# ProDoc_esp32_DWM1000_2025-11-09.net
KiCad netlist of a schematic drawn in EasyEDA Pro
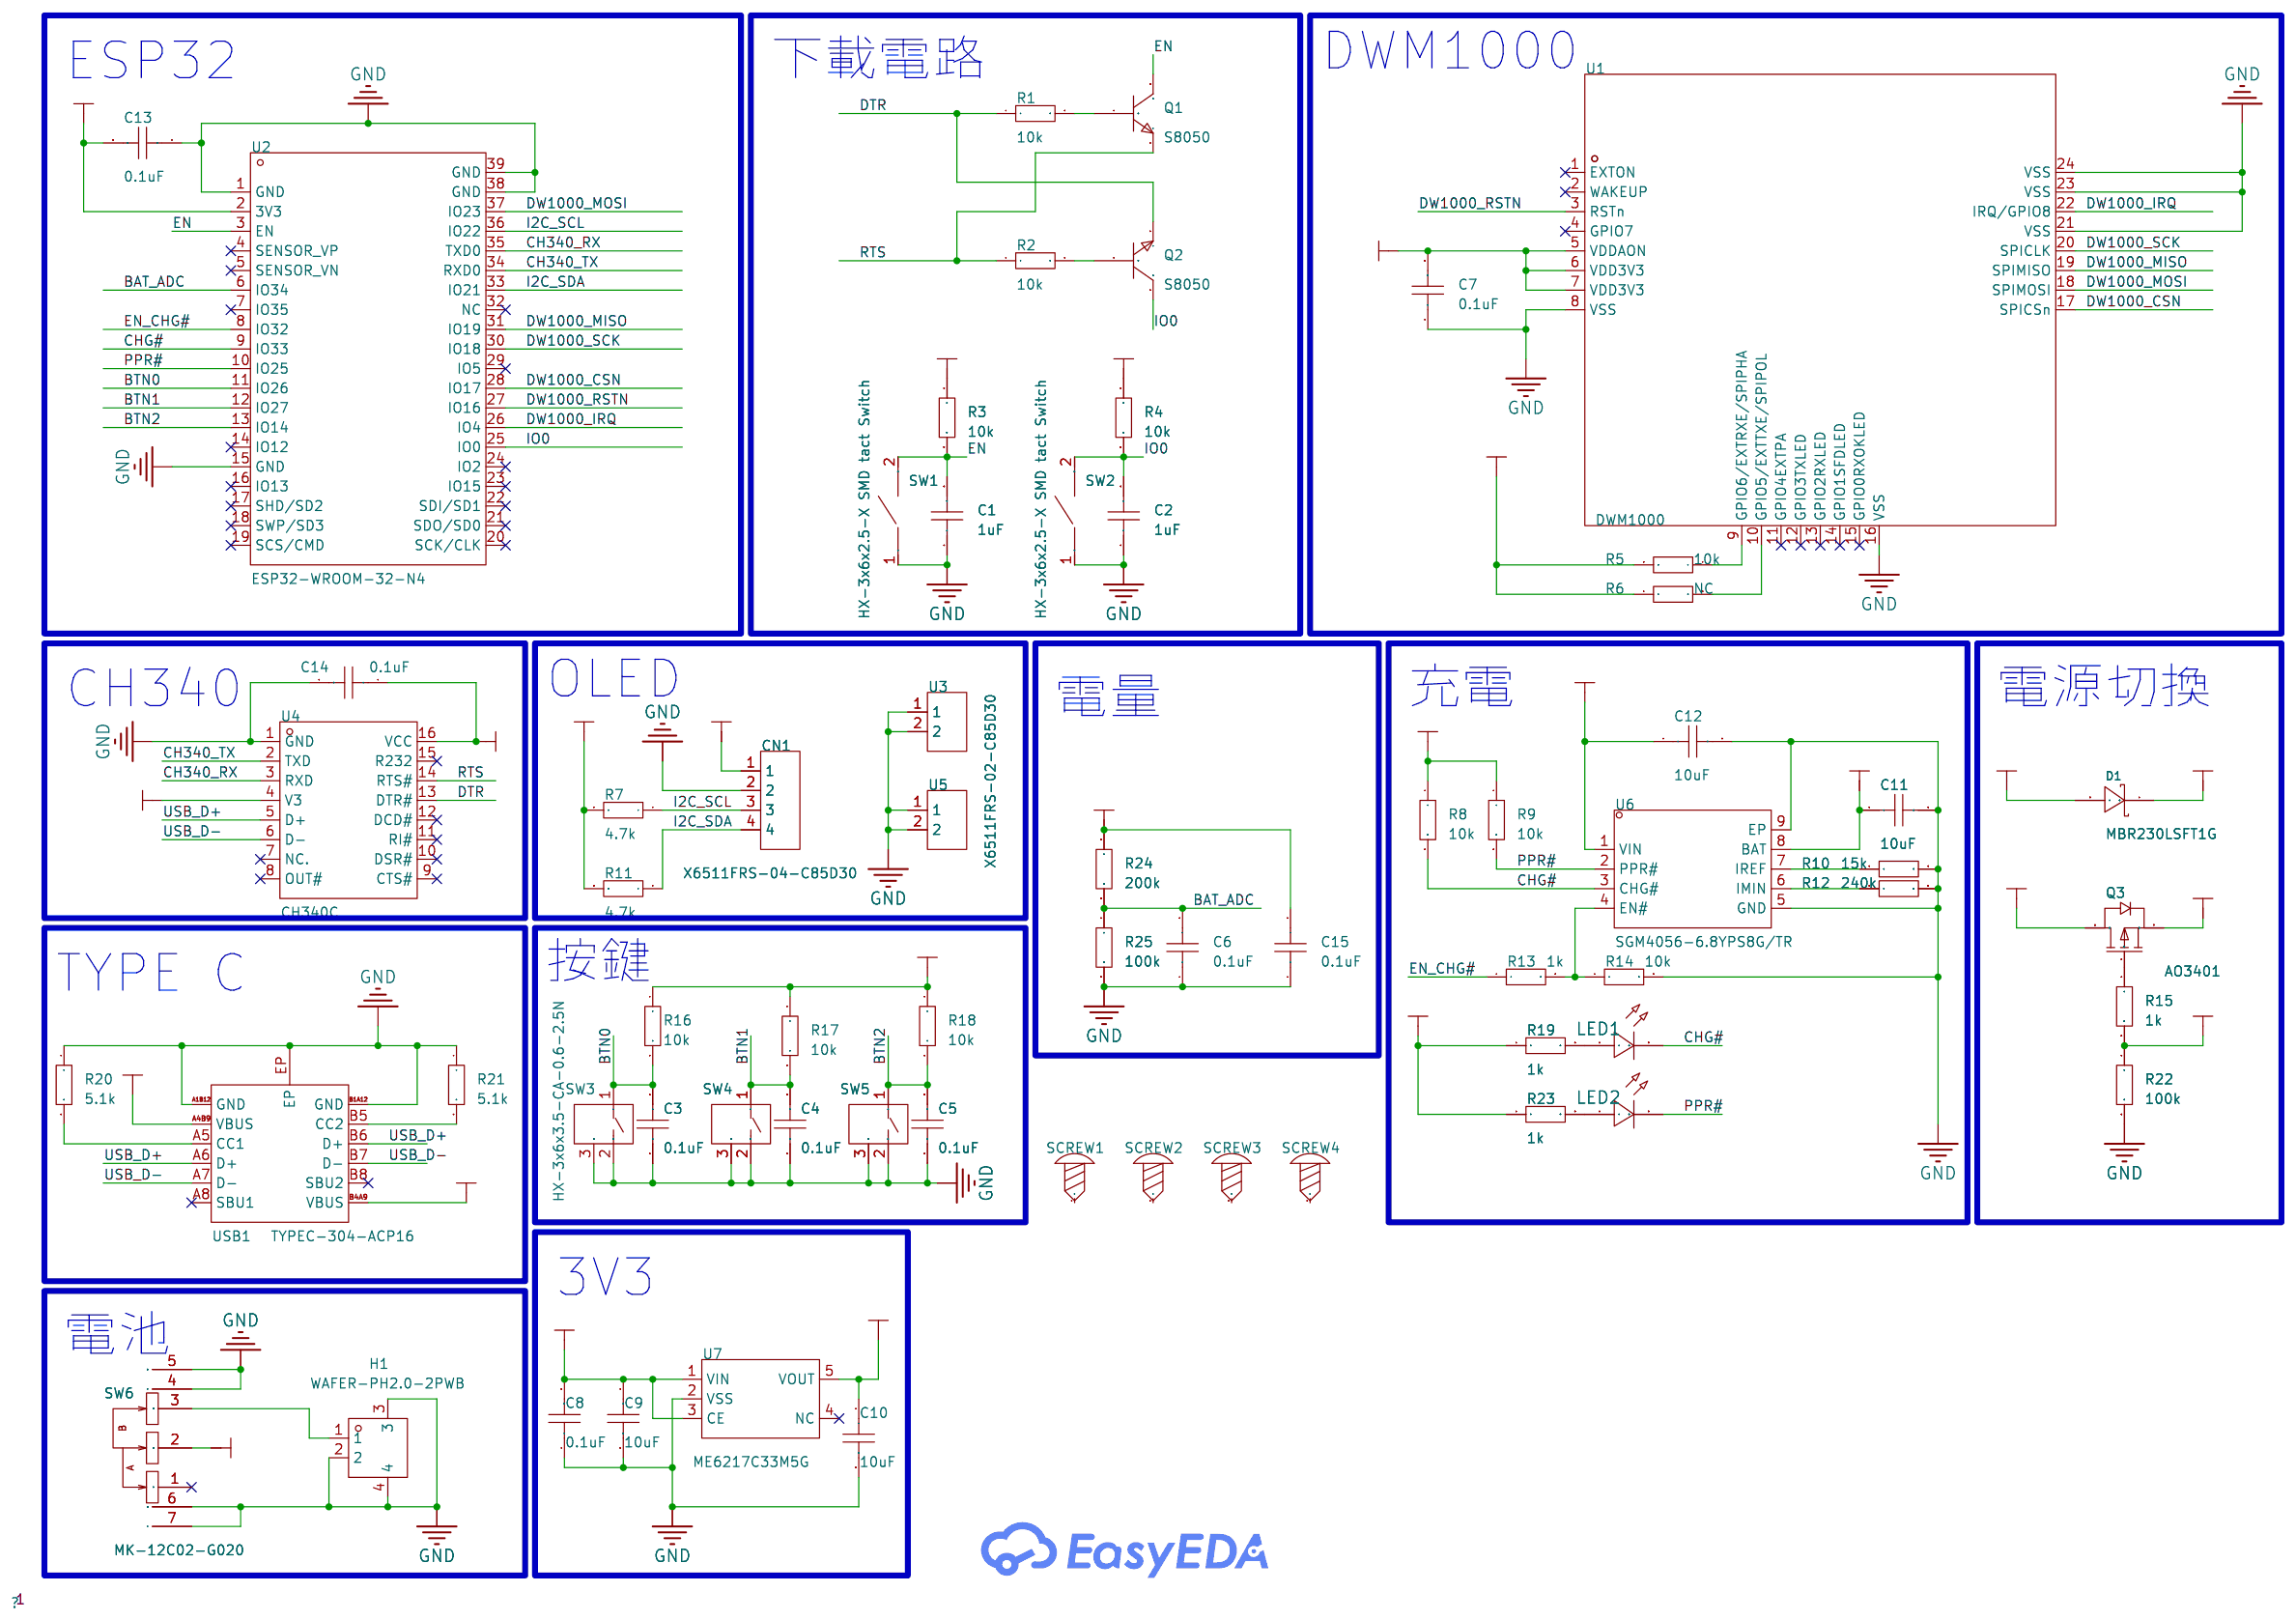
[diagram p0: schematic sheet]

(export (version "E")
  (design (tool "Eeschema 10.0.6"))
  (components
    (comp (ref "C1") (value "1uF") (footprint "easyedapro:C0805") (libsource (lib "easyedapro") (part "CAP")))
    (comp (ref "C2") (value "1uF") (footprint "easyedapro:C0805") (libsource (lib "easyedapro") (part "CAP")))
    (comp (ref "C3")
      (value "0.1uF")
      (footprint "easyedapro:C0805")
      (libsource (lib "easyedapro") (part "CAP"))
    )
    (comp (ref "C4")
      (value "0.1uF")
      (footprint "easyedapro:C0805")
      (libsource (lib "easyedapro") (part "CAP"))
    )
    (comp (ref "C5")
      (value "0.1uF")
      (footprint "easyedapro:C0805")
      (libsource (lib "easyedapro") (part "CAP"))
    )
    (comp (ref "C6")
      (value "0.1uF")
      (footprint "easyedapro:C0805")
      (libsource (lib "easyedapro") (part "CAP"))
    )
    (comp (ref "C7")
      (value "0.1uF")
      (footprint "easyedapro:C0805")
      (libsource (lib "easyedapro") (part "CAP"))
    )
    (comp (ref "C8")
      (value "0.1uF")
      (footprint "easyedapro:C0805")
      (libsource (lib "easyedapro") (part "CAP"))
    )
    (comp (ref "C9")
      (value "10uF")
      (footprint "easyedapro:C0805")
      (libsource (lib "easyedapro") (part "CAP"))
    )
    (comp (ref "C10")
      (value "10uF")
      (footprint "easyedapro:C0805")
      (libsource (lib "easyedapro") (part "CAP"))
    )
    (comp (ref "C11")
      (value "10uF")
      (footprint "easyedapro:C0805")
      (libsource (lib "easyedapro") (part "CAP"))
    )
    (comp (ref "C12")
      (value "10uF")
      (footprint "easyedapro:C0805")
      (libsource (lib "easyedapro") (part "CAP"))
    )
    (comp (ref "C13")
      (value "0.1uF")
      (footprint "easyedapro:C0805")
      (libsource (lib "easyedapro") (part "CAP"))
    )
    (comp (ref "C14")
      (value "0.1uF")
      (footprint "easyedapro:C0805")
      (libsource (lib "easyedapro") (part "CAP"))
    )
    (comp (ref "C15")
      (value "0.1uF")
      (footprint "easyedapro:C0805")
      (libsource (lib "easyedapro") (part "CAP"))
    )
    (comp (ref "CN1")
      (value "X6511FRS-04-C85D30")
      (footprint "easyedapro:HDR-SMD_4P-P2.54-H-F")
      (fields (field (name "Manufacturer") "XKB Connection(中国星坤)"))
      (libsource (lib "easyedapro") (part "X6511FRS-04-C85D30"))
    )
    (comp (ref "D1")
      (value "MBR230LSFT1G")
      (footprint "easyedapro:SOD-123FL_L2.7-W1.8-LS3.8-RD")
      (fields (field (name "Manufacturer") "onsemi(安森美)"))
      (libsource (lib "easyedapro") (part "MBR230LSFT1G"))
    )
    (comp (ref "H1")
      (value "WAFER-PH2.0-2PWB")
      (footprint "easyedapro:CONN-SMD_2P-P2.00_XUNPU_WAFER-PH2.0-2PWB")
      (fields (field (name "Manufacturer") "XUNPU(讯普)"))
      (libsource (lib "easyedapro") (part "WAFER-PH2.0-2PWB"))
    )
    (comp (ref "LED1")
      (value "~")
      (footprint "easyedapro:LED0805-RD_GREEN")
      (libsource (lib "easyedapro") (part "LED_R"))
    )
    (comp (ref "LED2")
      (value "~")
      (footprint "easyedapro:LED0805-RD_GREEN")
      (libsource (lib "easyedapro") (part "LED_R"))
    )
    (comp (ref "Q1")
      (value "S8050")
      (footprint "easyedapro:SOT-23-3_L2.9-W1.3-P1.90-LS2.4-BR")
      (libsource (lib "easyedapro") (part "S8050_C139514"))
    )
    (comp (ref "Q2")
      (value "S8050")
      (footprint "easyedapro:SOT-23-3_L2.9-W1.3-P1.90-LS2.4-BR")
      (libsource (lib "easyedapro") (part "S8050_C139514"))
    )
    (comp (ref "Q3")
      (value "AO3401")
      (footprint "easyedapro:SOT-23-3_L2.9-W1.6-P1.90-LS2.8-BR")
      (fields (field (name "Manufacturer") "BLUE ROCKET(蓝箭)"))
      (libsource (lib "easyedapro") (part "AO3401_C305433"))
    )
    (comp (ref "R1")
      (value "10k")
      (footprint "easyedapro:R0603")
      (fields (field (name "Manufacturer Part") "SCR0805F10K") (field (name "Manufacturer") "VO(翔胜)"))
      (libsource (lib "easyedapro") (part "Res"))
    )
    (comp (ref "R2")
      (value "10k")
      (footprint "easyedapro:R0603")
      (fields (field (name "Manufacturer Part") "SCR0805F10K") (field (name "Manufacturer") "VO(翔胜)"))
      (libsource (lib "easyedapro") (part "Res"))
    )
    (comp (ref "R3") (value "10k") (footprint "easyedapro:R0603") (libsource (lib "easyedapro") (part "Res")))
    (comp (ref "R4") (value "10k") (footprint "easyedapro:R0603") (libsource (lib "easyedapro") (part "Res")))
    (comp (ref "R5")
      (value "10k")
      (footprint "easyedapro:R0603")
      (fields (field (name "Manufacturer Part") "SCR0805F10K") (field (name "Manufacturer") "VO(翔胜)"))
      (libsource (lib "easyedapro") (part "Res"))
    )
    (comp (ref "R6")
      (value "NC")
      (footprint "easyedapro:R0603")
      (fields (field (name "Manufacturer Part") "SCR0805F10K") (field (name "Manufacturer") "VO(翔胜)"))
      (libsource (lib "easyedapro") (part "Res"))
    )
    (comp (ref "R7")
      (value "4.7k")
      (footprint "easyedapro:R0603")
      (fields (field (name "Manufacturer Part") "SCR0805F10K") (field (name "Manufacturer") "VO(翔胜)"))
      (libsource (lib "easyedapro") (part "Res"))
    )
    (comp (ref "R8")
      (value "10k")
      (footprint "easyedapro:R0603")
      (fields (field (name "Manufacturer Part") "SCR0805F10K") (field (name "Manufacturer") "VO(翔胜)"))
      (libsource (lib "easyedapro") (part "Res"))
    )
    (comp (ref "R9")
      (value "10k")
      (footprint "easyedapro:R0603")
      (fields (field (name "Manufacturer Part") "SCR0805F10K") (field (name "Manufacturer") "VO(翔胜)"))
      (libsource (lib "easyedapro") (part "Res"))
    )
    (comp (ref "R10")
      (value "15k")
      (footprint "easyedapro:R0603")
      (fields (field (name "Manufacturer Part") "SCR0805F10K") (field (name "Manufacturer") "VO(翔胜)"))
      (libsource (lib "easyedapro") (part "Res"))
    )
    (comp (ref "R11")
      (value "4.7k")
      (footprint "easyedapro:R0603")
      (fields (field (name "Manufacturer Part") "SCR0805F10K") (field (name "Manufacturer") "VO(翔胜)"))
      (libsource (lib "easyedapro") (part "Res"))
    )
    (comp (ref "R12")
      (value "240k")
      (footprint "easyedapro:R0603")
      (fields (field (name "Manufacturer Part") "SCR0805F10K") (field (name "Manufacturer") "VO(翔胜)"))
      (libsource (lib "easyedapro") (part "Res"))
    )
    (comp (ref "R13")
      (value "1k")
      (footprint "easyedapro:R0603")
      (fields (field (name "Manufacturer Part") "SCR0805F10K") (field (name "Manufacturer") "VO(翔胜)"))
      (libsource (lib "easyedapro") (part "Res"))
    )
    (comp (ref "R14")
      (value "10k")
      (footprint "easyedapro:R0603")
      (libsource (lib "easyedapro") (part "Res"))
    )
    (comp (ref "R15")
      (value "1k")
      (footprint "easyedapro:R0603")
      (fields (field (name "Manufacturer Part") "SCR0805F10K") (field (name "Manufacturer") "VO(翔胜)"))
      (libsource (lib "easyedapro") (part "Res"))
    )
    (comp (ref "R16")
      (value "10k")
      (footprint "easyedapro:R0603")
      (libsource (lib "easyedapro") (part "Res"))
    )
    (comp (ref "R17")
      (value "10k")
      (footprint "easyedapro:R0603")
      (libsource (lib "easyedapro") (part "Res"))
    )
    (comp (ref "R18")
      (value "10k")
      (footprint "easyedapro:R0603")
      (libsource (lib "easyedapro") (part "Res"))
    )
    (comp (ref "R19")
      (value "1k")
      (footprint "easyedapro:R0603")
      (fields (field (name "Manufacturer Part") "SCR0805F10K") (field (name "Manufacturer") "VO(翔胜)"))
      (libsource (lib "easyedapro") (part "Res"))
    )
    (comp (ref "R20")
      (value "5.1k")
      (footprint "easyedapro:R0603")
      (fields (field (name "Manufacturer Part") "SCR0805F10K") (field (name "Manufacturer") "VO(翔胜)"))
      (libsource (lib "easyedapro") (part "Res"))
    )
    (comp (ref "R21")
      (value "5.1k")
      (footprint "easyedapro:R0603")
      (fields (field (name "Manufacturer Part") "SCR0805F10K") (field (name "Manufacturer") "VO(翔胜)"))
      (libsource (lib "easyedapro") (part "Res"))
    )
    (comp (ref "R22")
      (value "100k")
      (footprint "easyedapro:R0603")
      (fields (field (name "Manufacturer Part") "SCR0805F10K") (field (name "Manufacturer") "VO(翔胜)"))
      (libsource (lib "easyedapro") (part "Res"))
    )
    (comp (ref "R23")
      (value "1k")
      (footprint "easyedapro:R0603")
      (fields (field (name "Manufacturer Part") "SCR0805F10K") (field (name "Manufacturer") "VO(翔胜)"))
      (libsource (lib "easyedapro") (part "Res"))
    )
    (comp (ref "R24")
      (value "200k")
      (footprint "easyedapro:R0603")
      (fields (field (name "Manufacturer Part") "SCR0805F10K") (field (name "Manufacturer") "VO(翔胜)"))
      (libsource (lib "easyedapro") (part "Res"))
    )
    (comp (ref "R25")
      (value "100k")
      (footprint "easyedapro:R0603")
      (fields (field (name "Manufacturer Part") "SCR0805F10K") (field (name "Manufacturer") "VO(翔胜)"))
      (libsource (lib "easyedapro") (part "Res"))
    )
    (comp (ref "SCREW1")
      (value "~")
      (footprint "easyedapro:Screw-Hole-M3")
      (libsource (lib "easyedapro") (part "Screw-Hole"))
    )
    (comp (ref "SCREW2")
      (value "~")
      (footprint "easyedapro:Screw-Hole-M3")
      (libsource (lib "easyedapro") (part "Screw-Hole"))
    )
    (comp (ref "SCREW3")
      (value "~")
      (footprint "easyedapro:Screw-Hole-M3")
      (libsource (lib "easyedapro") (part "Screw-Hole"))
    )
    (comp (ref "SCREW4")
      (value "~")
      (footprint "easyedapro:Screw-Hole-M3")
      (libsource (lib "easyedapro") (part "Screw-Hole"))
    )
    (comp (ref "SW1")
      (value "HX-3x6x2.5-X SMD tact Switch")
      (footprint "easyedapro:SW-SMD_HX-3X6X2.5-X")
      (fields (field (name "Manufacturer") "hanxia(韩下)"))
      (libsource (lib "easyedapro") (part "HX-3X6X2.5-X SMD TACT SWITCH"))
    )
    (comp (ref "SW2")
      (value "HX-3x6x2.5-X SMD tact Switch")
      (footprint "easyedapro:SW-SMD_HX-3X6X2.5-X")
      (fields (field (name "Manufacturer") "hanxia(韩下)"))
      (libsource (lib "easyedapro") (part "HX-3X6X2.5-X SMD TACT SWITCH"))
    )
    (comp (ref "SW3")
      (value "HX-3x6x3.5-CA-0.6-2.5N")
      (footprint "easyedapro:SW-SMD_HX-3X6X3.5-CA-0.6-2.5N")
      (fields (field (name "Manufacturer") "hanxia(韩下)"))
      (libsource (lib "easyedapro") (part "HX-3X6X3.5-CA-0.6-2.5N"))
    )
    (comp (ref "SW4")
      (value "HX-3x6x3.5-CA-0.6-2.5N")
      (footprint "easyedapro:SW-SMD_HX-3X6X3.5-CA-0.6-2.5N")
      (fields (field (name "Manufacturer") "hanxia(韩下)"))
      (libsource (lib "easyedapro") (part "HX-3X6X3.5-CA-0.6-2.5N"))
    )
    (comp (ref "SW5")
      (value "HX-3x6x3.5-CA-0.6-2.5N")
      (footprint "easyedapro:SW-SMD_HX-3X6X3.5-CA-0.6-2.5N")
      (fields (field (name "Manufacturer") "hanxia(韩下)"))
      (libsource (lib "easyedapro") (part "HX-3X6X3.5-CA-0.6-2.5N"))
    )
    (comp (ref "SW6")
      (value "MK-12C02-G020")
      (footprint "easyedapro:SW-SMD_MK-12C02-G020")
      (fields (field (name "Manufacturer") "G-Switch(品赞)"))
      (libsource (lib "easyedapro") (part "MK-12C02-G020"))
    )
    (comp (ref "U1")
      (value "DWM1000")
      (footprint "easyedapro:WIRELM-TH_DWM1000")
      (fields (field (name "Manufacturer") "decaWave"))
      (libsource (lib "easyedapro") (part "DWM1000"))
    )
    (comp (ref "U2")
      (value "ESP32-WROOM-32-N4")
      (footprint "easyedapro:WIFIM-SMD_ESP32-WROOM-32-N4")
      (fields (field (name "Manufacturer") "ESPRESSIF(乐鑫)"))
      (libsource (lib "easyedapro") (part "ESP32-WROOM-32"))
    )
    (comp (ref "U3")
      (value "X6511FRS-02-C85D30")
      (footprint "easyedapro:HDR-SMD_2P-P2.54-H-F-L11.5")
      (fields (field (name "Manufacturer") "XKB Connection(中国星坤)"))
      (libsource (lib "easyedapro") (part "X6511FRS-02-C85D30"))
    )
    (comp (ref "U4")
      (value "CH340C")
      (footprint "easyedapro:SOP-16_L10.0-W3.9-P1.27-LS6.0-BL")
      (fields (field (name "Manufacturer") "WCH(南京沁恒)"))
      (libsource (lib "easyedapro") (part "CH340C"))
    )
    (comp (ref "U5")
      (value "X6511FRS-02-C85D30")
      (footprint "easyedapro:HDR-SMD_2P-P2.54-H-F-L11.5")
      (fields (field (name "Manufacturer") "XKB Connection(中国星坤)"))
      (libsource (lib "easyedapro") (part "X6511FRS-02-C85D30"))
    )
    (comp (ref "U6")
      (value "SGM4056-6.8YPS8G/TR")
      (footprint "easyedapro:SOIC-8_L4.9-W3.9-P1.27-LS6.0-BL-EP")
      (fields (field (name "Manufacturer") "SGMICRO(圣邦微)"))
      (libsource (lib "easyedapro") (part "SGM4056-6.8YPS8G/TR"))
    )
    (comp (ref "U7")
      (value "ME6217C33M5G")
      (footprint "easyedapro:SOT-23-5_L3.0-W1.7-P0.95-LS2.8-BR")
      (fields (field (name "Manufacturer") "MICRONE(南京微盟)"))
      (libsource (lib "easyedapro") (part "ME6217C33M5G"))
    )
    (comp (ref "USB1")
      (value "TYPEC-304-ACP16")
      (footprint "easyedapro:USB-C-SMD_TYPE-C-16P-1")
      (fields (field (name "Manufacturer") "XUNPU(讯普)"))
      (libsource (lib "easyedapro") (part "TYPEC-304-ACP16"))
    )
  )
  (nets
    (net (code "1") (name "/BAT_ADC") (class "Default")
      (node (ref "C6") (pin "2") (pinfunction "2_2") (pintype "input"))
      (node (ref "R24") (pin "2") (pinfunction "2_2") (pintype "input"))
      (node (ref "R25") (pin "1") (pinfunction "1_1") (pintype "input"))
      (node (ref "U2") (pin "6") (pinfunction "IO34_6") (pintype "unspecified"))
    )
    (net (code "2") (name "/BTN0") (class "Default")
      (node (ref "C3") (pin "2") (pinfunction "2_2") (pintype "input"))
      (node (ref "R16") (pin "2") (pinfunction "2_2") (pintype "input"))
      (node (ref "SW3") (pin "1") (pinfunction "1_1") (pintype "unspecified"))
      (node (ref "U2") (pin "11") (pinfunction "IO26_11") (pintype "unspecified"))
    )
    (net (code "3") (name "/BTN1") (class "Default")
      (node (ref "C4") (pin "2") (pinfunction "2_2") (pintype "input"))
      (node (ref "R17") (pin "2") (pinfunction "2_2") (pintype "input"))
      (node (ref "SW4") (pin "1") (pinfunction "1_1") (pintype "unspecified"))
      (node (ref "U2") (pin "12") (pinfunction "IO27_12") (pintype "unspecified"))
    )
    (net (code "4") (name "/BTN2") (class "Default")
      (node (ref "C5") (pin "2") (pinfunction "2_2") (pintype "input"))
      (node (ref "R18") (pin "2") (pinfunction "2_2") (pintype "input"))
      (node (ref "SW5") (pin "1") (pinfunction "1_1") (pintype "unspecified"))
      (node (ref "U2") (pin "13") (pinfunction "IO14_13") (pintype "unspecified"))
    )
    (net (code "5") (name "/CH340_RX") (class "Default")
      (node (ref "U2") (pin "35") (pinfunction "TXD0_35") (pintype "unspecified"))
      (node (ref "U4") (pin "3") (pinfunction "RXD_3") (pintype "unspecified"))
    )
    (net (code "6") (name "/CH340_TX") (class "Default")
      (node (ref "U2") (pin "34") (pinfunction "RXD0_34") (pintype "unspecified"))
      (node (ref "U4") (pin "2") (pinfunction "TXD_2") (pintype "unspecified"))
    )
    (net (code "7") (name "/CHG#") (class "Default")
      (node (ref "LED1") (pin "2") (pinfunction "C_2") (pintype "input"))
      (node (ref "R8") (pin "2") (pinfunction "2_2") (pintype "input"))
      (node (ref "U2") (pin "9") (pinfunction "IO33_9") (pintype "unspecified"))
      (node (ref "U6") (pin "3") (pinfunction "CHG#_3") (pintype "unspecified"))
    )
    (net (code "8") (name "/DTR") (class "Default")
      (node (ref "Q2") (pin "2") (pinfunction "E_2") (pintype "input"))
      (node (ref "R1") (pin "1") (pinfunction "1_1") (pintype "input"))
      (node (ref "U4") (pin "13") (pinfunction "DTR#_13") (pintype "unspecified"))
    )
    (net (code "9") (name "/DW1000_CSN") (class "Default")
      (node (ref "U1") (pin "17") (pinfunction "SPICSn_17") (pintype "unspecified"))
      (node (ref "U2") (pin "28") (pinfunction "IO17_28") (pintype "unspecified"))
    )
    (net (code "10") (name "/DW1000_IRQ") (class "Default")
      (node (ref "U1") (pin "22") (pinfunction "IRQ/GPIO8_22") (pintype "unspecified"))
      (node (ref "U2") (pin "26") (pinfunction "IO4_26") (pintype "unspecified"))
    )
    (net (code "11") (name "/DW1000_MISO") (class "Default")
      (node (ref "U1") (pin "19") (pinfunction "SPIMISO_19") (pintype "unspecified"))
      (node (ref "U2") (pin "31") (pinfunction "IO19_31") (pintype "unspecified"))
    )
    (net (code "12") (name "/DW1000_MOSI") (class "Default")
      (node (ref "U1") (pin "18") (pinfunction "SPIMOSI_18") (pintype "unspecified"))
      (node (ref "U2") (pin "37") (pinfunction "IO23_37") (pintype "unspecified"))
    )
    (net (code "13") (name "/DW1000_RSTN") (class "Default")
      (node (ref "U1") (pin "3") (pinfunction "RSTn_3") (pintype "unspecified"))
      (node (ref "U2") (pin "27") (pinfunction "IO16_27") (pintype "unspecified"))
    )
    (net (code "14") (name "/DW1000_SCK") (class "Default")
      (node (ref "U1") (pin "20") (pinfunction "SPICLK_20") (pintype "unspecified"))
      (node (ref "U2") (pin "30") (pinfunction "IO18_30") (pintype "unspecified"))
    )
    (net (code "15") (name "/EN") (class "Default")
      (node (ref "C1") (pin "2") (pinfunction "2_2") (pintype "input"))
      (node (ref "Q1") (pin "3") (pinfunction "C_3") (pintype "input"))
      (node (ref "R3") (pin "2") (pinfunction "2_2") (pintype "input"))
      (node (ref "SW1") (pin "2") (pinfunction "2_2") (pintype "unspecified"))
      (node (ref "U2") (pin "3") (pinfunction "EN_3") (pintype "unspecified"))
    )
    (net (code "16") (name "/EN_CHG#") (class "Default")
      (node (ref "R13") (pin "1") (pinfunction "1_1") (pintype "input"))
      (node (ref "U2") (pin "8") (pinfunction "IO32_8") (pintype "unspecified"))
    )
    (net (code "17") (name "/I2C_SCL") (class "Default")
      (node (ref "CN1") (pin "3") (pinfunction "3_3") (pintype "unspecified"))
      (node (ref "R7") (pin "1") (pinfunction "1_1") (pintype "input"))
      (node (ref "U2") (pin "36") (pinfunction "IO22_36") (pintype "unspecified"))
    )
    (net (code "18") (name "/I2C_SDA") (class "Default")
      (node (ref "CN1") (pin "4") (pinfunction "4_4") (pintype "unspecified"))
      (node (ref "R11") (pin "1") (pinfunction "1_1") (pintype "input"))
      (node (ref "U2") (pin "33") (pinfunction "IO21_33") (pintype "unspecified"))
    )
    (net (code "19") (name "/IO0") (class "Default")
      (node (ref "C2") (pin "2") (pinfunction "2_2") (pintype "input"))
      (node (ref "Q2") (pin "3") (pinfunction "C_3") (pintype "input"))
      (node (ref "R4") (pin "2") (pinfunction "2_2") (pintype "input"))
      (node (ref "SW2") (pin "2") (pinfunction "2_2") (pintype "unspecified"))
      (node (ref "U2") (pin "25") (pinfunction "IO0_25") (pintype "unspecified"))
    )
    (net (code "20") (name "/PPR#") (class "Default")
      (node (ref "LED2") (pin "2") (pinfunction "C_2") (pintype "input"))
      (node (ref "R9") (pin "2") (pinfunction "2_2") (pintype "input"))
      (node (ref "U2") (pin "10") (pinfunction "IO25_10") (pintype "unspecified"))
      (node (ref "U6") (pin "2") (pinfunction "PPR#_2") (pintype "unspecified"))
    )
    (net (code "21") (name "/RTS") (class "Default")
      (node (ref "Q1") (pin "2") (pinfunction "E_2") (pintype "input"))
      (node (ref "R2") (pin "1") (pinfunction "1_1") (pintype "input"))
      (node (ref "U4") (pin "14") (pinfunction "RTS#_14") (pintype "unspecified"))
    )
    (net (code "22") (name "/USB_D+") (class "Default")
      (node (ref "U4") (pin "5") (pinfunction "D+_5") (pintype "unspecified"))
      (node (ref "USB1") (pin "A6") (pinfunction "D+_A6") (pintype "unspecified"))
      (node (ref "USB1") (pin "B6") (pinfunction "D+_B6") (pintype "unspecified"))
    )
    (net (code "23") (name "/USB_D-") (class "Default")
      (node (ref "U4") (pin "6") (pinfunction "D-_6") (pintype "unspecified"))
      (node (ref "USB1") (pin "A7") (pinfunction "D-_A7") (pintype "unspecified"))
      (node (ref "USB1") (pin "B7") (pinfunction "D-_B7") (pintype "unspecified"))
    )
    (net (code "24") (name "3V3") (class "Default")
      (node (ref "C10") (pin "1") (pinfunction "1_1") (pintype "input"))
      (node (ref "C13") (pin "2") (pinfunction "2_2") (pintype "input"))
      (node (ref "C14") (pin "1") (pinfunction "1_1") (pintype "input"))
      (node (ref "C7") (pin "2") (pinfunction "2_2") (pintype "input"))
      (node (ref "CN1") (pin "1") (pinfunction "1_1") (pintype "unspecified"))
      (node (ref "R11") (pin "2") (pinfunction "2_2") (pintype "input"))
      (node (ref "R16") (pin "1") (pinfunction "1_1") (pintype "input"))
      (node (ref "R17") (pin "1") (pinfunction "1_1") (pintype "input"))
      (node (ref "R18") (pin "1") (pinfunction "1_1") (pintype "input"))
      (node (ref "R19") (pin "1") (pinfunction "1_1") (pintype "input"))
      (node (ref "R23") (pin "1") (pinfunction "1_1") (pintype "input"))
      (node (ref "R3") (pin "1") (pinfunction "1_1") (pintype "input"))
      (node (ref "R4") (pin "1") (pinfunction "1_1") (pintype "input"))
      (node (ref "R5") (pin "2") (pinfunction "2_2") (pintype "input"))
      (node (ref "R6") (pin "1") (pinfunction "1_1") (pintype "input"))
      (node (ref "R7") (pin "2") (pinfunction "2_2") (pintype "input"))
      (node (ref "R8") (pin "1") (pinfunction "1_1") (pintype "input"))
      (node (ref "R9") (pin "1") (pinfunction "1_1") (pintype "input"))
      (node (ref "U1") (pin "5") (pinfunction "VDDAON_5") (pintype "unspecified"))
      (node (ref "U1") (pin "6") (pinfunction "VDD3V3_6") (pintype "unspecified"))
      (node (ref "U1") (pin "7") (pinfunction "VDD3V3_7") (pintype "unspecified"))
      (node (ref "U2") (pin "2") (pinfunction "3V3_2") (pintype "unspecified"))
      (node (ref "U4") (pin "16") (pinfunction "VCC_16") (pintype "unspecified"))
      (node (ref "U4") (pin "4") (pinfunction "V3_4") (pintype "unspecified"))
      (node (ref "U7") (pin "5") (pinfunction "VOUT_5") (pintype "unspecified"))
    )
    (net (code "25") (name "5V") (class "Default")
      (node (ref "C12") (pin "1") (pinfunction "1_1") (pintype "input"))
      (node (ref "D1") (pin "2") (pinfunction "A_2") (pintype "input"))
      (node (ref "R15") (pin "2") (pinfunction "2_2") (pintype "input"))
      (node (ref "R22") (pin "1") (pinfunction "1_1") (pintype "input"))
      (node (ref "U6") (pin "1") (pinfunction "VIN_1") (pintype "unspecified"))
      (node (ref "USB1") (pin "A4B9") (pinfunction "VBUS_A4B9") (pintype "unspecified"))
      (node (ref "USB1") (pin "B4A9") (pinfunction "VBUS_B4A9") (pintype "unspecified"))
    )
    (net (code "26") (name "GND") (class "Default")
      (node (ref "C1") (pin "1") (pinfunction "1_1") (pintype "input"))
      (node (ref "C10") (pin "2") (pinfunction "2_2") (pintype "input"))
      (node (ref "C11") (pin "2") (pinfunction "2_2") (pintype "input"))
      (node (ref "C12") (pin "2") (pinfunction "2_2") (pintype "input"))
      (node (ref "C13") (pin "1") (pinfunction "1_1") (pintype "input"))
      (node (ref "C14") (pin "2") (pinfunction "2_2") (pintype "input"))
      (node (ref "C15") (pin "1") (pinfunction "1_1") (pintype "input"))
      (node (ref "C2") (pin "1") (pinfunction "1_1") (pintype "input"))
      (node (ref "C3") (pin "1") (pinfunction "1_1") (pintype "input"))
      (node (ref "C4") (pin "1") (pinfunction "1_1") (pintype "input"))
      (node (ref "C5") (pin "1") (pinfunction "1_1") (pintype "input"))
      (node (ref "C6") (pin "1") (pinfunction "1_1") (pintype "input"))
      (node (ref "C7") (pin "1") (pinfunction "1_1") (pintype "input"))
      (node (ref "C8") (pin "1") (pinfunction "1_1") (pintype "input"))
      (node (ref "C9") (pin "2") (pinfunction "2_2") (pintype "input"))
      (node (ref "CN1") (pin "2") (pinfunction "2_2") (pintype "unspecified"))
      (node (ref "H1") (pin "2") (pinfunction "2_2") (pintype "unspecified"))
      (node (ref "H1") (pin "3") (pinfunction "3_3") (pintype "unspecified"))
      (node (ref "H1") (pin "4") (pinfunction "4_4") (pintype "unspecified"))
      (node (ref "R10") (pin "2") (pinfunction "2_2") (pintype "input"))
      (node (ref "R12") (pin "2") (pinfunction "2_2") (pintype "input"))
      (node (ref "R14") (pin "2") (pinfunction "2_2") (pintype "input"))
      (node (ref "R20") (pin "1") (pinfunction "1_1") (pintype "input"))
      (node (ref "R21") (pin "1") (pinfunction "1_1") (pintype "input"))
      (node (ref "R22") (pin "2") (pinfunction "2_2") (pintype "input"))
      (node (ref "R25") (pin "2") (pinfunction "2_2") (pintype "input"))
      (node (ref "SW1") (pin "1") (pinfunction "1_1") (pintype "unspecified"))
      (node (ref "SW2") (pin "1") (pinfunction "1_1") (pintype "unspecified"))
      (node (ref "SW3") (pin "2") (pinfunction "2_2") (pintype "unspecified"))
      (node (ref "SW3") (pin "3") (pinfunction "3_3") (pintype "unspecified"))
      (node (ref "SW4") (pin "2") (pinfunction "2_2") (pintype "unspecified"))
      (node (ref "SW4") (pin "3") (pinfunction "3_3") (pintype "unspecified"))
      (node (ref "SW5") (pin "2") (pinfunction "2_2") (pintype "unspecified"))
      (node (ref "SW5") (pin "3") (pinfunction "3_3") (pintype "unspecified"))
      (node (ref "SW6") (pin "4") (pinfunction "4_4") (pintype "unspecified"))
      (node (ref "SW6") (pin "5") (pinfunction "5_5") (pintype "unspecified"))
      (node (ref "SW6") (pin "6") (pinfunction "6_6") (pintype "unspecified"))
      (node (ref "SW6") (pin "7") (pinfunction "7_7") (pintype "unspecified"))
      (node (ref "U1") (pin "16") (pinfunction "VSS_16") (pintype "unspecified"))
      (node (ref "U1") (pin "21") (pinfunction "VSS_21") (pintype "unspecified"))
      (node (ref "U1") (pin "23") (pinfunction "VSS_23") (pintype "unspecified"))
      (node (ref "U1") (pin "24") (pinfunction "VSS_24") (pintype "unspecified"))
      (node (ref "U1") (pin "8") (pinfunction "VSS_8") (pintype "unspecified"))
      (node (ref "U2") (pin "1") (pinfunction "GND_1") (pintype "unspecified"))
      (node (ref "U2") (pin "15") (pinfunction "GND_15") (pintype "unspecified"))
      (node (ref "U2") (pin "38") (pinfunction "GND_38") (pintype "unspecified"))
      (node (ref "U2") (pin "39") (pinfunction "GND_39") (pintype "unspecified"))
      (node (ref "U3") (pin "1") (pinfunction "1_1") (pintype "unspecified"))
      (node (ref "U3") (pin "2") (pinfunction "2_2") (pintype "unspecified"))
      (node (ref "U4") (pin "1") (pinfunction "GND_1") (pintype "unspecified"))
      (node (ref "U5") (pin "1") (pinfunction "1_1") (pintype "unspecified"))
      (node (ref "U5") (pin "2") (pinfunction "2_2") (pintype "unspecified"))
      (node (ref "U6") (pin "5") (pinfunction "GND_5") (pintype "unspecified"))
      (node (ref "U6") (pin "9") (pinfunction "EP_9") (pintype "unspecified"))
      (node (ref "U7") (pin "2") (pinfunction "VSS_2") (pintype "unspecified"))
      (node (ref "USB1") (pin "A1B12") (pinfunction "GND_A1B12") (pintype "unspecified"))
      (node (ref "USB1") (pin "B1A12") (pinfunction "GND_B1A12") (pintype "unspecified"))
      (node (ref "USB1") (pin "EP") (pinfunction "EP_EP") (pintype "unspecified"))
    )
    (net (code "27") (name "Net-(H1-Pad1)") (class "Default")
      (node (ref "H1") (pin "1") (pinfunction "1_1") (pintype "unspecified"))
      (node (ref "SW6") (pin "3") (pinfunction "3_3") (pintype "unspecified"))
    )
    (net (code "28") (name "Net-(LED1-A)") (class "Default")
      (node (ref "LED1") (pin "1") (pinfunction "A_1") (pintype "input"))
      (node (ref "R19") (pin "2") (pinfunction "2_2") (pintype "input"))
    )
    (net (code "29") (name "Net-(LED2-A)") (class "Default")
      (node (ref "LED2") (pin "1") (pinfunction "A_1") (pintype "input"))
      (node (ref "R23") (pin "2") (pinfunction "2_2") (pintype "input"))
    )
    (net (code "30") (name "Net-(Q1-B)") (class "Default")
      (node (ref "Q1") (pin "1") (pinfunction "B_1") (pintype "input"))
      (node (ref "R1") (pin "2") (pinfunction "2_2") (pintype "input"))
    )
    (net (code "31") (name "Net-(Q2-B)") (class "Default")
      (node (ref "Q2") (pin "1") (pinfunction "B_1") (pintype "input"))
      (node (ref "R2") (pin "2") (pinfunction "2_2") (pintype "input"))
    )
    (net (code "32") (name "Net-(Q3-G)") (class "Default")
      (node (ref "Q3") (pin "1") (pinfunction "G_1") (pintype "unspecified"))
      (node (ref "R15") (pin "1") (pinfunction "1_1") (pintype "input"))
    )
    (net (code "33") (name "Net-(U1-GPIO5{slash}EXTTXE{slash}SPIPOL)") (class "Default")
      (node (ref "R6") (pin "2") (pinfunction "2_2") (pintype "input"))
      (node (ref "U1") (pin "10") (pinfunction "GPIO5/EXTTXE/SPIPOL_10") (pintype "unspecified"))
    )
    (net (code "34") (name "Net-(U1-GPIO6{slash}EXTRXE{slash}SPIPHA)") (class "Default")
      (node (ref "R5") (pin "1") (pinfunction "1_1") (pintype "input"))
      (node (ref "U1") (pin "9") (pinfunction "GPIO6/EXTRXE/SPIPHA_9") (pintype "unspecified"))
    )
    (net (code "35") (name "Net-(U6-EN#)") (class "Default")
      (node (ref "R13") (pin "2") (pinfunction "2_2") (pintype "input"))
      (node (ref "R14") (pin "1") (pinfunction "1_1") (pintype "input"))
      (node (ref "U6") (pin "4") (pinfunction "EN#_4") (pintype "unspecified"))
    )
    (net (code "36") (name "Net-(U6-IMIN)") (class "Default")
      (node (ref "R12") (pin "1") (pinfunction "1_1") (pintype "input"))
      (node (ref "U6") (pin "6") (pinfunction "IMIN_6") (pintype "unspecified"))
    )
    (net (code "37") (name "Net-(U6-IREF)") (class "Default")
      (node (ref "R10") (pin "1") (pinfunction "1_1") (pintype "input"))
      (node (ref "U6") (pin "7") (pinfunction "IREF_7") (pintype "unspecified"))
    )
    (net (code "38") (name "Net-(USB1-CC1)") (class "Default")
      (node (ref "R20") (pin "2") (pinfunction "2_2") (pintype "input"))
      (node (ref "USB1") (pin "A5") (pinfunction "CC1_A5") (pintype "unspecified"))
    )
    (net (code "39") (name "Net-(USB1-CC2)") (class "Default")
      (node (ref "R21") (pin "2") (pinfunction "2_2") (pintype "input"))
      (node (ref "USB1") (pin "B5") (pinfunction "CC2_B5") (pintype "unspecified"))
    )
    (net (code "40") (name "VBAT") (class "Default")
      (node (ref "C11") (pin "1") (pinfunction "1_1") (pintype "input"))
      (node (ref "C15") (pin "2") (pinfunction "2_2") (pintype "input"))
      (node (ref "Q3") (pin "3") (pinfunction "D_3") (pintype "unspecified"))
      (node (ref "R24") (pin "1") (pinfunction "1_1") (pintype "input"))
      (node (ref "SW6") (pin "2") (pinfunction "2_2") (pintype "unspecified"))
      (node (ref "U6") (pin "8") (pinfunction "BAT_8") (pintype "unspecified"))
    )
    (net (code "41") (name "VSYS") (class "Default")
      (node (ref "C8") (pin "2") (pinfunction "2_2") (pintype "input"))
      (node (ref "C9") (pin "1") (pinfunction "1_1") (pintype "input"))
      (node (ref "D1") (pin "1") (pinfunction "C_1") (pintype "input"))
      (node (ref "Q3") (pin "2") (pinfunction "S_2") (pintype "unspecified"))
      (node (ref "U7") (pin "1") (pinfunction "VIN_1") (pintype "unspecified"))
      (node (ref "U7") (pin "3") (pinfunction "CE_3") (pintype "unspecified"))
    )
    (net (code "42") (name "unconnected-(SCREW1-Pad1)") (class "Default")
      (node (ref "SCREW1") (pin "1") (pinfunction "1_1") (pintype "input"))
    )
    (net (code "43") (name "unconnected-(SCREW2-Pad1)") (class "Default")
      (node (ref "SCREW2") (pin "1") (pinfunction "1_1") (pintype "input"))
    )
    (net (code "44") (name "unconnected-(SCREW3-Pad1)") (class "Default")
      (node (ref "SCREW3") (pin "1") (pinfunction "1_1") (pintype "input"))
    )
    (net (code "45") (name "unconnected-(SCREW4-Pad1)") (class "Default")
      (node (ref "SCREW4") (pin "1") (pinfunction "1_1") (pintype "input"))
    )
    (net (code "46") (name "unconnected-(SW6-Pad1)") (class "Default")
      (node (ref "SW6") (pin "1") (pinfunction "1_1") (pintype "unspecified+no_connect"))
    )
    (net (code "47") (name "unconnected-(U1-EXTON-Pad1)") (class "Default")
      (node (ref "U1") (pin "1") (pinfunction "EXTON_1") (pintype "unspecified+no_connect"))
    )
    (net (code "48") (name "unconnected-(U1-GPIO0RXOKLED-Pad15)") (class "Default")
      (node (ref "U1") (pin "15") (pinfunction "GPIO0RXOKLED_15") (pintype "unspecified+no_connect"))
    )
    (net (code "49") (name "unconnected-(U1-GPIO1SFDLED-Pad14)") (class "Default")
      (node (ref "U1") (pin "14") (pinfunction "GPIO1SFDLED_14") (pintype "unspecified+no_connect"))
    )
    (net (code "50") (name "unconnected-(U1-GPIO2RXLED-Pad13)") (class "Default")
      (node (ref "U1") (pin "13") (pinfunction "GPIO2RXLED_13") (pintype "unspecified+no_connect"))
    )
    (net (code "51") (name "unconnected-(U1-GPIO3TXLED-Pad12)") (class "Default")
      (node (ref "U1") (pin "12") (pinfunction "GPIO3TXLED_12") (pintype "unspecified+no_connect"))
    )
    (net (code "52") (name "unconnected-(U1-GPIO4EXTPA-Pad11)") (class "Default")
      (node (ref "U1") (pin "11") (pinfunction "GPIO4EXTPA_11") (pintype "unspecified+no_connect"))
    )
    (net (code "53") (name "unconnected-(U1-GPIO7-Pad4)") (class "Default")
      (node (ref "U1") (pin "4") (pinfunction "GPIO7_4") (pintype "unspecified+no_connect"))
    )
    (net (code "54") (name "unconnected-(U1-WAKEUP-Pad2)") (class "Default")
      (node (ref "U1") (pin "2") (pinfunction "WAKEUP_2") (pintype "unspecified+no_connect"))
    )
    (net (code "55") (name "unconnected-(U2-IO2-Pad24)") (class "Default")
      (node (ref "U2") (pin "24") (pinfunction "IO2_24") (pintype "unspecified+no_connect"))
    )
    (net (code "56") (name "unconnected-(U2-IO5-Pad29)") (class "Default")
      (node (ref "U2") (pin "29") (pinfunction "IO5_29") (pintype "unspecified+no_connect"))
    )
    (net (code "57") (name "unconnected-(U2-IO12-Pad14)") (class "Default")
      (node (ref "U2") (pin "14") (pinfunction "IO12_14") (pintype "unspecified+no_connect"))
    )
    (net (code "58") (name "unconnected-(U2-IO13-Pad16)") (class "Default")
      (node (ref "U2") (pin "16") (pinfunction "IO13_16") (pintype "unspecified+no_connect"))
    )
    (net (code "59") (name "unconnected-(U2-IO15-Pad23)") (class "Default")
      (node (ref "U2") (pin "23") (pinfunction "IO15_23") (pintype "unspecified+no_connect"))
    )
    (net (code "60") (name "unconnected-(U2-IO35-Pad7)") (class "Default")
      (node (ref "U2") (pin "7") (pinfunction "IO35_7") (pintype "unspecified+no_connect"))
    )
    (net (code "61") (name "unconnected-(U2-NC-Pad32)") (class "Default")
      (node (ref "U2") (pin "32") (pinfunction "NC_32") (pintype "unspecified+no_connect"))
    )
    (net (code "62") (name "unconnected-(U2-SCK{slash}CLK-Pad20)") (class "Default")
      (node (ref "U2") (pin "20") (pinfunction "SCK/CLK_20") (pintype "unspecified+no_connect"))
    )
    (net (code "63") (name "unconnected-(U2-SCS{slash}CMD-Pad19)") (class "Default")
      (node (ref "U2") (pin "19") (pinfunction "SCS/CMD_19") (pintype "unspecified+no_connect"))
    )
    (net (code "64") (name "unconnected-(U2-SDI{slash}SD1-Pad22)") (class "Default")
      (node (ref "U2") (pin "22") (pinfunction "SDI/SD1_22") (pintype "unspecified+no_connect"))
    )
    (net (code "65") (name "unconnected-(U2-SDO{slash}SD0-Pad21)") (class "Default")
      (node (ref "U2") (pin "21") (pinfunction "SDO/SD0_21") (pintype "unspecified+no_connect"))
    )
    (net (code "66") (name "unconnected-(U2-SENSOR_VN-Pad5)") (class "Default")
      (node (ref "U2") (pin "5") (pinfunction "SENSOR_VN_5") (pintype "unspecified+no_connect"))
    )
    (net (code "67") (name "unconnected-(U2-SENSOR_VP-Pad4)") (class "Default")
      (node (ref "U2") (pin "4") (pinfunction "SENSOR_VP_4") (pintype "unspecified+no_connect"))
    )
    (net (code "68") (name "unconnected-(U2-SHD{slash}SD2-Pad17)") (class "Default")
      (node (ref "U2") (pin "17") (pinfunction "SHD/SD2_17") (pintype "unspecified+no_connect"))
    )
    (net (code "69") (name "unconnected-(U2-SWP{slash}SD3-Pad18)") (class "Default")
      (node (ref "U2") (pin "18") (pinfunction "SWP/SD3_18") (pintype "unspecified+no_connect"))
    )
    (net (code "70") (name "unconnected-(U4-CTS#-Pad9)") (class "Default")
      (node (ref "U4") (pin "9") (pinfunction "CTS#_9") (pintype "unspecified+no_connect"))
    )
    (net (code "71") (name "unconnected-(U4-DCD#-Pad12)") (class "Default")
      (node (ref "U4") (pin "12") (pinfunction "DCD#_12") (pintype "unspecified+no_connect"))
    )
    (net (code "72") (name "unconnected-(U4-DSR#-Pad10)") (class "Default")
      (node (ref "U4") (pin "10") (pinfunction "DSR#_10") (pintype "unspecified+no_connect"))
    )
    (net (code "73") (name "unconnected-(U4-NC.-Pad7)") (class "Default")
      (node (ref "U4") (pin "7") (pinfunction "NC._7") (pintype "unspecified+no_connect"))
    )
    (net (code "74") (name "unconnected-(U4-OUT#-Pad8)") (class "Default")
      (node (ref "U4") (pin "8") (pinfunction "OUT#_8") (pintype "unspecified+no_connect"))
    )
    (net (code "75") (name "unconnected-(U4-R232-Pad15)") (class "Default")
      (node (ref "U4") (pin "15") (pinfunction "R232_15") (pintype "unspecified+no_connect"))
    )
    (net (code "76") (name "unconnected-(U4-RI#-Pad11)") (class "Default")
      (node (ref "U4") (pin "11") (pinfunction "RI#_11") (pintype "unspecified+no_connect"))
    )
    (net (code "77") (name "unconnected-(U7-NC-Pad4)") (class "Default")
      (node (ref "U7") (pin "4") (pinfunction "NC_4") (pintype "unspecified+no_connect"))
    )
    (net (code "78") (name "unconnected-(USB1-SBU1-PadA8)") (class "Default")
      (node (ref "USB1") (pin "A8") (pinfunction "SBU1_A8") (pintype "unspecified+no_connect"))
    )
    (net (code "79") (name "unconnected-(USB1-SBU2-PadB8)") (class "Default")
      (node (ref "USB1") (pin "B8") (pinfunction "SBU2_B8") (pintype "unspecified+no_connect"))
    )
  )
)
